# 1-Schematic_LNA_Bias_Tee_powered_filteri.net
KiCad netlist of a schematic drawn in EasyEDA
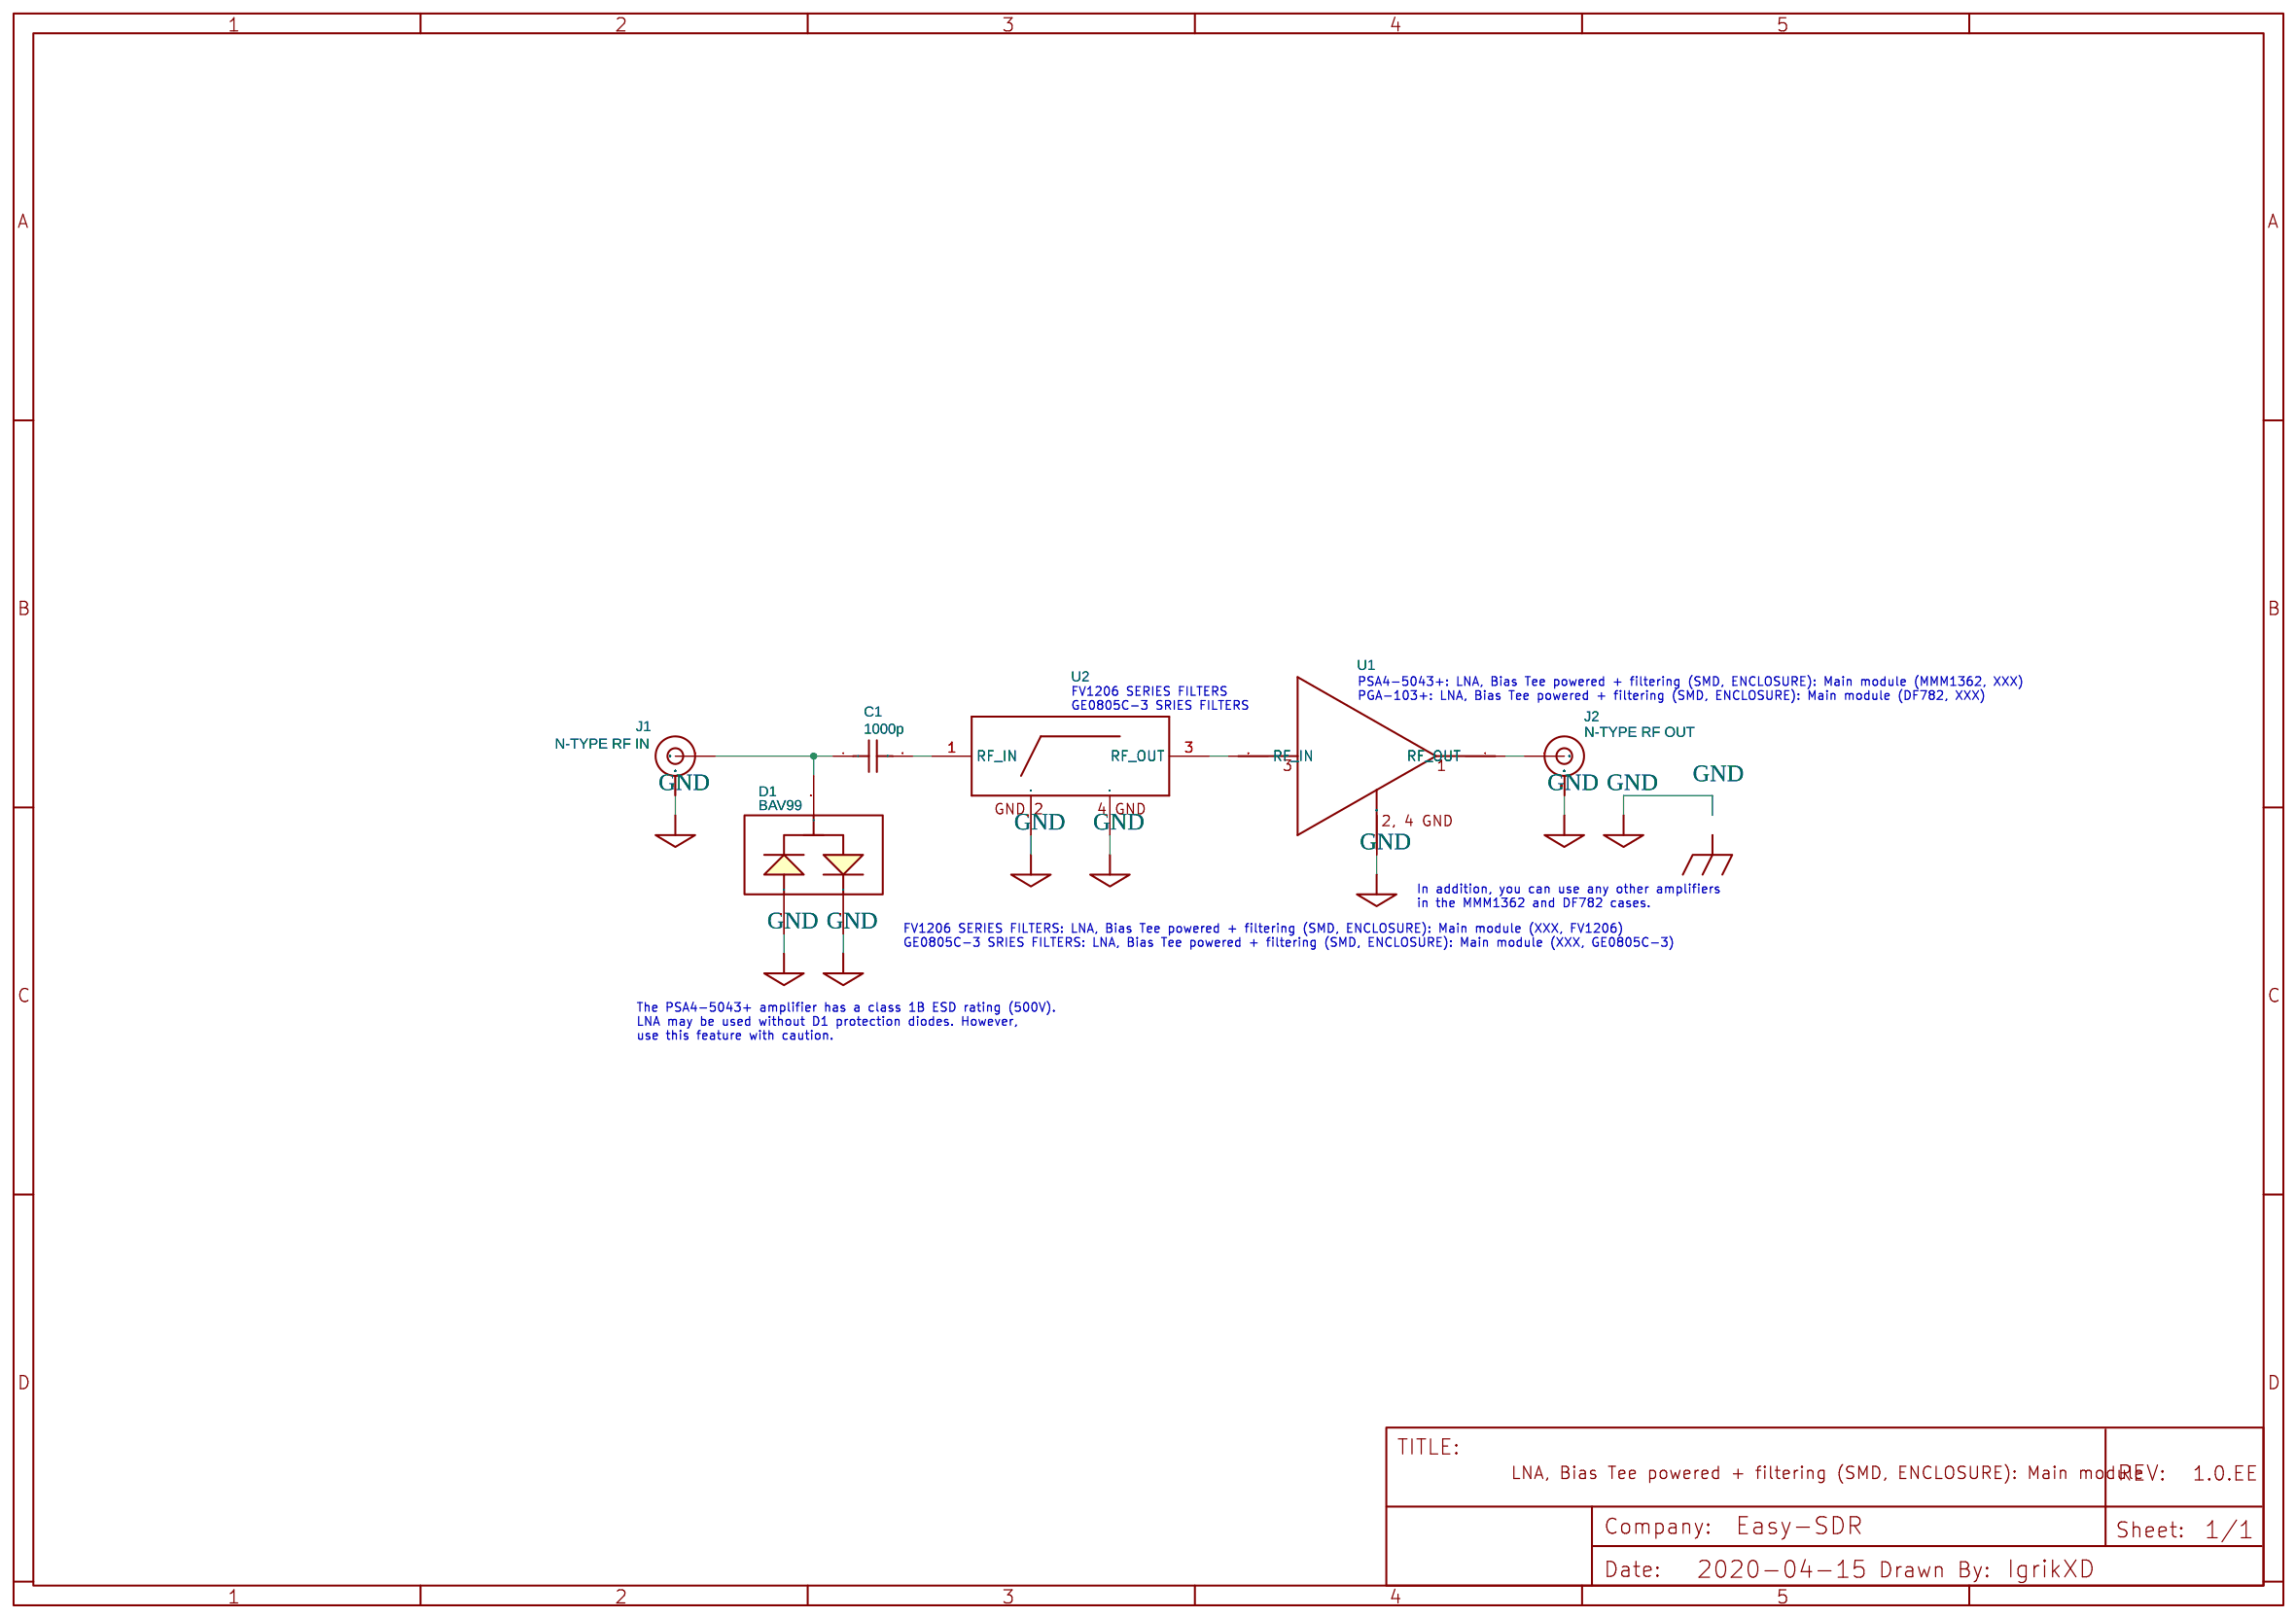
[diagram p0: schematic sheet]

(export (version "E")
  (design (tool "Eeschema 10.0.6"))
  (components
    (comp (ref "C1")
      (value "1000p")
      (fields
        (field (name "BOM_Manufacturer Part") "0603N102G500CT")
        (field (name "BOM_Supplier Part") "C338154")
      )
      (libsource (lib "") (part "Capacitor"))
    )
    (comp (ref "D1")
      (value "BAV99")
      (fields (field (name "BOM_Supplier Part") "C83868"))
      (libsource (lib "") (part "Unknown_405_-370"))
    )
    (comp (ref "J1")
      (value "N-TYPE RF IN")
      (fields
        (field (name "BOM_Manufacturer Part") "82-97-RFX")
        (field (name "BOM_Supplier Part") "ARFX1023-ND")
      )
      (libsource (lib "") (part "Unknown_340_-410"))
    )
    (comp (ref "J2")
      (value "N-TYPE RF OUT")
      (fields
        (field (name "BOM_Manufacturer Part") "82-97-RFX")
        (field (name "BOM_Supplier Part") "ARFX1023-ND")
      )
      (libsource (lib "") (part "Unknown_780_-410"))
    )
    (comp (ref "U1") (value "PSA4-5043+") (libsource (lib "") (part "PSA4-5043+")))
    (comp (ref "U2") (value "FV1206 SERIES FILTERS") (libsource (lib "") (part "HPF-FV1206")))
  )
  (nets
    (net (code "1") (name "GND") (class "Default")
      (node (ref "D1") (pin "1") (pinfunction "1_1") (pintype "unspecified"))
      (node (ref "D1") (pin "2") (pinfunction "2_2") (pintype "unspecified"))
      (node (ref "J1") (pin "1") (pinfunction "GND_1") (pintype "unspecified"))
      (node (ref "J1") (pin "3") (pinfunction "GND_3") (pintype "unspecified"))
      (node (ref "J1") (pin "4") (pinfunction "GND_4") (pintype "unspecified"))
      (node (ref "J1") (pin "5") (pinfunction "GND_5") (pintype "unspecified"))
      (node (ref "J2") (pin "1") (pinfunction "GND_1") (pintype "unspecified"))
      (node (ref "J2") (pin "3") (pinfunction "GND_3") (pintype "unspecified"))
      (node (ref "J2") (pin "4") (pinfunction "GND_4") (pintype "unspecified"))
      (node (ref "J2") (pin "5") (pinfunction "GND_5") (pintype "unspecified"))
      (node (ref "U1") (pin "2") (pinfunction "GND_2") (pintype "unspecified"))
      (node (ref "U1") (pin "4") (pinfunction "GND_4") (pintype "unspecified"))
      (node (ref "U2") (pin "2") (pinfunction "GND_2") (pintype "unspecified"))
      (node (ref "U2") (pin "4") (pinfunction "GND_4") (pintype "unspecified"))
    )
    (net (code "2") (name "Net-(J1-SIGNAL)") (class "Default")
      (node (ref "C1") (pin "1") (pinfunction "1_1") (pintype "unspecified"))
      (node (ref "D1") (pin "3") (pinfunction "3_3") (pintype "unspecified"))
      (node (ref "J1") (pin "2") (pinfunction "SIGNAL_2") (pintype "unspecified"))
    )
    (net (code "3") (name "Net-(J2-SIGNAL)") (class "Default")
      (node (ref "J2") (pin "2") (pinfunction "SIGNAL_2") (pintype "unspecified"))
      (node (ref "U1") (pin "1") (pinfunction "RF_OUT_1") (pintype "unspecified"))
    )
    (net (code "4") (name "Net-(U1-RF_IN)") (class "Default")
      (node (ref "U1") (pin "3") (pinfunction "RF_IN_3") (pintype "unspecified"))
      (node (ref "U2") (pin "3") (pinfunction "RF_OUT_3") (pintype "unspecified"))
    )
    (net (code "5") (name "Net-(U2-RF_IN)") (class "Default")
      (node (ref "C1") (pin "2") (pinfunction "2_2") (pintype "unspecified"))
      (node (ref "U2") (pin "1") (pinfunction "RF_IN_1") (pintype "unspecified"))
    )
  )
)
